# Anthe.net
KiCad netlist of a schematic drawn in EAGLE
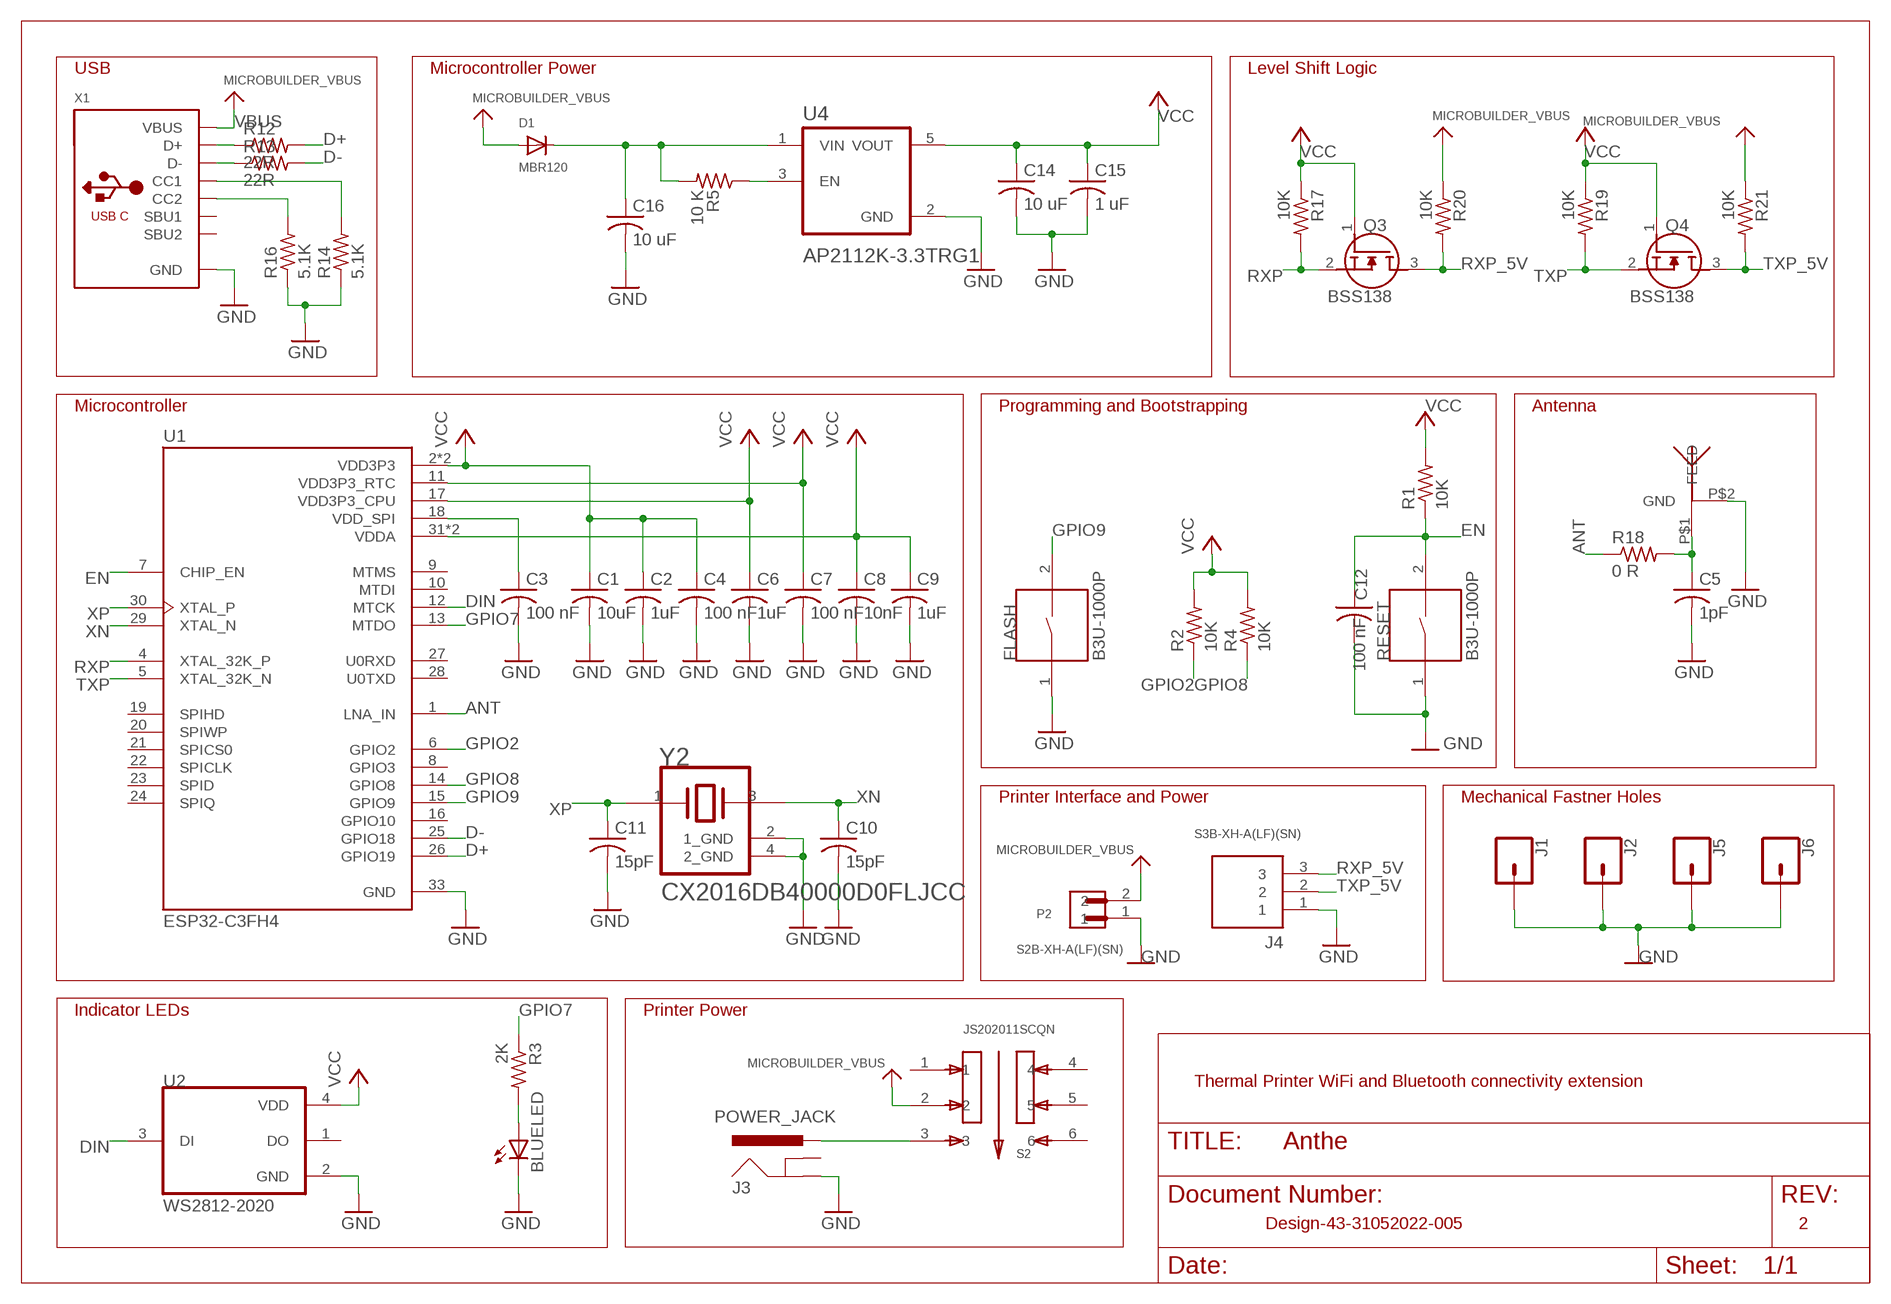
[diagram p0: schematic, sheet 1]

(export (version "E")
  (design (tool "Eeschema 10.0.6"))
  (components
    (comp (ref "BLUELED")
      (value "LEDCHIPLED_0603")
      (footprint "eagle-import:CHIPLED_0603")
      (libsource (lib "eagle-import") (part "LEDCHIPLED_0603"))
    )
    (comp (ref "C1")
      (value "10uF")
      (footprint "eagle-import:C0402")
      (libsource (lib "eagle-import") (part "C-USC0402"))
    )
    (comp (ref "C2")
      (value "1uF")
      (footprint "eagle-import:C0402")
      (libsource (lib "eagle-import") (part "C-USC0402"))
    )
    (comp (ref "C3")
      (value "100 nF")
      (footprint "eagle-import:C0402")
      (libsource (lib "eagle-import") (part "C-USC0402"))
    )
    (comp (ref "C4")
      (value "100 nF")
      (footprint "eagle-import:C0402")
      (libsource (lib "eagle-import") (part "C-USC0402"))
    )
    (comp (ref "C5")
      (value "1pF")
      (footprint "eagle-import:C0402")
      (libsource (lib "eagle-import") (part "C-USC0402"))
    )
    (comp (ref "C6")
      (value "1uF")
      (footprint "eagle-import:C0402")
      (libsource (lib "eagle-import") (part "C-USC0402"))
    )
    (comp (ref "C7")
      (value "100 nF")
      (footprint "eagle-import:C0402")
      (libsource (lib "eagle-import") (part "C-USC0402"))
    )
    (comp (ref "C8")
      (value "10nF")
      (footprint "eagle-import:C0402")
      (libsource (lib "eagle-import") (part "C-USC0402"))
    )
    (comp (ref "C9")
      (value "1uF")
      (footprint "eagle-import:C0402")
      (libsource (lib "eagle-import") (part "C-USC0402"))
    )
    (comp (ref "C10")
      (value "15pF")
      (footprint "eagle-import:C0402")
      (libsource (lib "eagle-import") (part "C-USC0402"))
    )
    (comp (ref "C11")
      (value "15pF")
      (footprint "eagle-import:C0402")
      (libsource (lib "eagle-import") (part "C-USC0402"))
    )
    (comp (ref "C12")
      (value "100 nF")
      (footprint "eagle-import:C0402")
      (libsource (lib "eagle-import") (part "C-USC0402"))
    )
    (comp (ref "C14")
      (value "10 uF")
      (footprint "eagle-import:C0402")
      (libsource (lib "eagle-import") (part "C-USC0402"))
    )
    (comp (ref "C15")
      (value "1 uF")
      (footprint "eagle-import:C0402")
      (libsource (lib "eagle-import") (part "C-USC0402"))
    )
    (comp (ref "C16")
      (value "10 uF")
      (footprint "eagle-import:C0402")
      (libsource (lib "eagle-import") (part "C-USC0402"))
    )
    (comp (ref "D1")
      (value "MBR120")
      (footprint "eagle-import:SOD-123")
      (libsource (lib "eagle-import") (part "DIODESOD-123"))
    )
    (comp (ref "FLASH")
      (value "B3U-1000P")
      (footprint "eagle-import:SW_B3U-1000P")
      (fields (field (name "MF") "Omron"))
      (libsource (lib "eagle-import") (part "B3U-1000P"))
    )
    (comp (ref "J1")
      (value "CONN_01PTH_2MM")
      (footprint "eagle-import:1X01_2MM")
      (libsource (lib "eagle-import") (part "CONN_01PTH_2MM"))
    )
    (comp (ref "J2")
      (value "CONN_01PTH_2MM")
      (footprint "eagle-import:1X01_2MM")
      (libsource (lib "eagle-import") (part "CONN_01PTH_2MM"))
    )
    (comp (ref "J3")
      (value "POWER_JACK")
      (footprint "eagle-import:POWER_JACK_PTH")
      (libsource (lib "eagle-import") (part "POWER_JACK"))
    )
    (comp (ref "J4")
      (value "S3B-XH-A(LF)(SN)")
      (footprint "eagle-import:JST_S3B-XH-A(LF)(SN)")
      (fields (field (name "MF") "JST Sales America Inc."))
      (libsource (lib "eagle-import") (part "S3B-XH-A(LF)(SN)"))
    )
    (comp (ref "J5")
      (value "CONN_01PTH_2MM")
      (footprint "eagle-import:1X01_2MM")
      (libsource (lib "eagle-import") (part "CONN_01PTH_2MM"))
    )
    (comp (ref "J6")
      (value "CONN_01PTH_2MM")
      (footprint "eagle-import:1X01_2MM")
      (libsource (lib "eagle-import") (part "CONN_01PTH_2MM"))
    )
    (comp (ref "P2")
      (value "S2B-XH-A(LF)(SN)")
      (footprint "eagle-import:JST_S2B-XH-A(LF)(SN)")
      (fields (field (name "MF") "JST Sales") (field (name "MP") "S2B-XH-A (LF)(SN)"))
      (libsource (lib "eagle-import") (part "S2B-XH-A(LF)(SN)"))
    )
    (comp (ref "Q3")
      (value "BSS138")
      (footprint "eagle-import:SOT95P240X120-3N")
      (fields (field (name "MOUSER_PART_NUMBER") "512-BSS138"))
      (libsource (lib "eagle-import") (part "BSS138"))
    )
    (comp (ref "Q4")
      (value "BSS138")
      (footprint "eagle-import:SOT95P240X120-3N")
      (fields (field (name "MOUSER_PART_NUMBER") "512-BSS138"))
      (libsource (lib "eagle-import") (part "BSS138"))
    )
    (comp (ref "R1")
      (value "10K")
      (footprint "eagle-import:R0402")
      (libsource (lib "eagle-import") (part "R-US_R0402"))
    )
    (comp (ref "R2")
      (value "10K")
      (footprint "eagle-import:R0402")
      (libsource (lib "eagle-import") (part "R-US_R0402"))
    )
    (comp (ref "R3")
      (value "2K")
      (footprint "eagle-import:R0402")
      (libsource (lib "eagle-import") (part "R-US_R0402"))
    )
    (comp (ref "R4")
      (value "10K")
      (footprint "eagle-import:R0402")
      (libsource (lib "eagle-import") (part "R-US_R0402"))
    )
    (comp (ref "R5")
      (value "10 K")
      (footprint "eagle-import:R0402")
      (libsource (lib "eagle-import") (part "R-US_R0402"))
    )
    (comp (ref "R12")
      (value "22R")
      (footprint "eagle-import:R0402")
      (libsource (lib "eagle-import") (part "R-US_R0402"))
    )
    (comp (ref "R13")
      (value "22R")
      (footprint "eagle-import:R0402")
      (libsource (lib "eagle-import") (part "R-US_R0402"))
    )
    (comp (ref "R14")
      (value "5.1K")
      (footprint "eagle-import:R0402")
      (libsource (lib "eagle-import") (part "R-US_R0402"))
    )
    (comp (ref "R16")
      (value "5.1K")
      (footprint "eagle-import:R0402")
      (libsource (lib "eagle-import") (part "R-US_R0402"))
    )
    (comp (ref "R17")
      (value "10K")
      (footprint "eagle-import:R0402")
      (libsource (lib "eagle-import") (part "R-US_R0402"))
    )
    (comp (ref "R18")
      (value "0 R")
      (footprint "eagle-import:R0402")
      (libsource (lib "eagle-import") (part "R-US_R0402"))
    )
    (comp (ref "R19")
      (value "10K")
      (footprint "eagle-import:R0402")
      (libsource (lib "eagle-import") (part "R-US_R0402"))
    )
    (comp (ref "R20")
      (value "10K")
      (footprint "eagle-import:R0402")
      (libsource (lib "eagle-import") (part "R-US_R0402"))
    )
    (comp (ref "R21")
      (value "10K")
      (footprint "eagle-import:R0402")
      (libsource (lib "eagle-import") (part "R-US_R0402"))
    )
    (comp (ref "RESET")
      (value "B3U-1000P")
      (footprint "eagle-import:SW_B3U-1000P")
      (fields (field (name "MF") "Omron"))
      (libsource (lib "eagle-import") (part "B3U-1000P"))
    )
    (comp (ref "S2")
      (value "JS202011SCQN")
      (footprint "eagle-import:SW_JS202011SCQN")
      (fields (field (name "MF") "C&K"))
      (libsource (lib "eagle-import") (part "JS202011SCQN"))
    )
    (comp (ref "U$3")
      (value "PCB_ANTENNA_WIFI")
      (footprint "eagle-import:WIFI_ANTENNA")
      (libsource (lib "eagle-import") (part "PCB_ANTENNA_WIFI"))
    )
    (comp (ref "U1")
      (value "ESP32-C3FH4")
      (footprint "eagle-import:QFN50P500X500X90-33N")
      (fields (field (name "MF") "Espressif Systems"))
      (libsource (lib "eagle-import") (part "ESP32-C3FH4"))
    )
    (comp (ref "U2")
      (value "WS2812-2020")
      (footprint "eagle-import:LED_WS2812-2020")
      (fields (field (name "MF") "Worldsemi"))
      (libsource (lib "eagle-import") (part "WS2812-2020"))
    )
    (comp (ref "U4")
      (value "AP2112K-3.3TRG1")
      (footprint "eagle-import:SOT95P285X140-5N")
      (fields (field (name "MF") "Diodes Inc."))
      (libsource (lib "eagle-import") (part "AP2112K-3.3TRG1"))
    )
    (comp (ref "X1")
      (value "MICROBUILDER_USB_C")
      (footprint "eagle-import:MICROBUILDER_USB_C_CUSB31-CFM2AX-01-X")
      (libsource (lib "eagle-import") (part "MICROBUILDER_USB_C"))
    )
    (comp (ref "Y2")
      (value "KYOCERA_INTERNATIONAL_INC._ELECTRONIC_COMPONENTS_CX2016DB40000D0FLJCCKYOCERA_INTERNATIONAL_INC._ELECTRONIC_COMPONENTS_CX2016DB40000D0FLJCC_0_0")
      (footprint "eagle-import:KYOCERA_INTERNATIONAL_INC._ELECTRONIC_COMPONENTS_CX2016DB40000D0FLJCC_0")
      (fields
        (field (name "DIGIKEY_PART_NUMBER") "1253-1120-1-ND")
        (field (name "MF") "Kyocera International Inc. Electronic Components")
        (field (name "MOUSER_PART_NUMBER") "581-CX2016DB40DFLJCC")
      )
      (libsource (lib "eagle-import") (part "KYOCERA_INTERNATIONAL_INC._ELECTRONIC_COMPONENTS_CX2016DB40000D0FLJCCKYOCERA_INTERNATIONAL_INC._ELECTRONIC_COMPONENTS_CX2016DB40000D0FLJCC_0_0"))
    )
  )
  (nets
    (net (code "1") (name "/ANT") (class "Default")
      (node (ref "R18") (pin "1") (pinfunction "1_1") (pintype "passive"))
      (node (ref "U1") (pin "1") (pinfunction "LNA_IN_1") (pintype "bidirectional"))
    )
    (net (code "2") (name "/D+") (class "Default")
      (node (ref "R12") (pin "2") (pinfunction "2_2") (pintype "passive"))
      (node (ref "U1") (pin "26") (pinfunction "GPIO19_26") (pintype "bidirectional"))
    )
    (net (code "3") (name "/D-") (class "Default")
      (node (ref "R13") (pin "2") (pinfunction "2_2") (pintype "passive"))
      (node (ref "U1") (pin "25") (pinfunction "GPIO18_25") (pintype "bidirectional"))
    )
    (net (code "4") (name "/DIN") (class "Default")
      (node (ref "U1") (pin "12") (pinfunction "MTCK_12") (pintype "bidirectional"))
      (node (ref "U2") (pin "3") (pinfunction "DI_3") (pintype "input"))
    )
    (net (code "5") (name "/EN") (class "Default")
      (node (ref "C12") (pin "1") (pinfunction "1_1") (pintype "passive"))
      (node (ref "R1") (pin "1") (pinfunction "1_1") (pintype "passive"))
      (node (ref "RESET") (pin "2") (pinfunction "2_2") (pintype "passive"))
      (node (ref "U1") (pin "7") (pinfunction "CHIP_EN_7") (pintype "input"))
    )
    (net (code "6") (name "/GPIO2") (class "Default")
      (node (ref "R2") (pin "1") (pinfunction "1_1") (pintype "passive"))
      (node (ref "U1") (pin "6") (pinfunction "GPIO2_6") (pintype "bidirectional"))
    )
    (net (code "7") (name "/GPIO7") (class "Default")
      (node (ref "R3") (pin "1") (pinfunction "1_1") (pintype "passive"))
      (node (ref "U1") (pin "13") (pinfunction "MTDO_13") (pintype "bidirectional"))
    )
    (net (code "8") (name "/GPIO8") (class "Default")
      (node (ref "R4") (pin "1") (pinfunction "1_1") (pintype "passive"))
      (node (ref "U1") (pin "14") (pinfunction "GPIO8_14") (pintype "bidirectional"))
    )
    (net (code "9") (name "/GPIO9") (class "Default")
      (node (ref "FLASH") (pin "2") (pinfunction "2_2") (pintype "passive"))
      (node (ref "U1") (pin "15") (pinfunction "GPIO9_15") (pintype "bidirectional"))
    )
    (net (code "10") (name "/RXP") (class "Default")
      (node (ref "Q3") (pin "2") (pinfunction "S_2") (pintype "bidirectional"))
      (node (ref "R17") (pin "2") (pinfunction "2_2") (pintype "passive"))
      (node (ref "U1") (pin "4") (pinfunction "XTAL_32K_P_4") (pintype "bidirectional"))
    )
    (net (code "11") (name "/RXP_5V") (class "Default")
      (node (ref "J4") (pin "3") (pinfunction "3_3") (pintype "passive"))
      (node (ref "Q3") (pin "3") (pinfunction "D_3") (pintype "bidirectional"))
      (node (ref "R20") (pin "2") (pinfunction "2_2") (pintype "passive"))
    )
    (net (code "12") (name "/TXP") (class "Default")
      (node (ref "Q4") (pin "2") (pinfunction "S_2") (pintype "bidirectional"))
      (node (ref "R19") (pin "2") (pinfunction "2_2") (pintype "passive"))
      (node (ref "U1") (pin "5") (pinfunction "XTAL_32K_N_5") (pintype "bidirectional"))
    )
    (net (code "13") (name "/TXP_5V") (class "Default")
      (node (ref "J4") (pin "2") (pinfunction "2_2") (pintype "passive"))
      (node (ref "Q4") (pin "3") (pinfunction "D_3") (pintype "bidirectional"))
      (node (ref "R21") (pin "2") (pinfunction "2_2") (pintype "passive"))
    )
    (net (code "14") (name "/XN") (class "Default")
      (node (ref "C10") (pin "1") (pinfunction "1_1") (pintype "passive"))
      (node (ref "U1") (pin "29") (pinfunction "XTAL_N_29") (pintype "output"))
      (node (ref "Y2") (pin "3") (pinfunction "3_3") (pintype "passive"))
    )
    (net (code "15") (name "/XP") (class "Default")
      (node (ref "C11") (pin "1") (pinfunction "1_1") (pintype "passive"))
      (node (ref "U1") (pin "30") (pinfunction "XTAL_P_30") (pintype "input"))
      (node (ref "Y2") (pin "1") (pinfunction "1_1") (pintype "passive"))
    )
    (net (code "16") (name "GND") (class "Default")
      (node (ref "BLUELED") (pin "C") (pinfunction "C_C") (pintype "passive"))
      (node (ref "C1") (pin "2") (pinfunction "2_2") (pintype "passive"))
      (node (ref "C10") (pin "2") (pinfunction "2_2") (pintype "passive"))
      (node (ref "C11") (pin "2") (pinfunction "2_2") (pintype "passive"))
      (node (ref "C12") (pin "2") (pinfunction "2_2") (pintype "passive"))
      (node (ref "C14") (pin "2") (pinfunction "2_2") (pintype "passive"))
      (node (ref "C15") (pin "2") (pinfunction "2_2") (pintype "passive"))
      (node (ref "C16") (pin "2") (pinfunction "2_2") (pintype "passive"))
      (node (ref "C2") (pin "2") (pinfunction "2_2") (pintype "passive"))
      (node (ref "C3") (pin "2") (pinfunction "2_2") (pintype "passive"))
      (node (ref "C4") (pin "2") (pinfunction "2_2") (pintype "passive"))
      (node (ref "C5") (pin "2") (pinfunction "2_2") (pintype "passive"))
      (node (ref "C6") (pin "2") (pinfunction "2_2") (pintype "passive"))
      (node (ref "C7") (pin "2") (pinfunction "2_2") (pintype "passive"))
      (node (ref "C8") (pin "2") (pinfunction "2_2") (pintype "passive"))
      (node (ref "C9") (pin "2") (pinfunction "2_2") (pintype "passive"))
      (node (ref "FLASH") (pin "1") (pinfunction "1_1") (pintype "passive"))
      (node (ref "J1") (pin "1") (pinfunction "1_1") (pintype "passive"))
      (node (ref "J2") (pin "1") (pinfunction "1_1") (pintype "passive"))
      (node (ref "J3") (pin "GND") (pinfunction "GND_GND") (pintype "bidirectional"))
      (node (ref "J4") (pin "1") (pinfunction "1_1") (pintype "passive"))
      (node (ref "J5") (pin "1") (pinfunction "1_1") (pintype "passive"))
      (node (ref "J6") (pin "1") (pinfunction "1_1") (pintype "passive"))
      (node (ref "P2") (pin "1") (pinfunction "1_1") (pintype "passive"))
      (node (ref "R14") (pin "1") (pinfunction "1_1") (pintype "passive"))
      (node (ref "R16") (pin "1") (pinfunction "1_1") (pintype "passive"))
      (node (ref "RESET") (pin "1") (pinfunction "1_1") (pintype "passive"))
      (node (ref "U$3") (pin "P$2") (pinfunction "GND_P$2") (pintype "output"))
      (node (ref "U1") (pin "33") (pinfunction "GND_33") (pintype "power_in"))
      (node (ref "U2") (pin "2") (pinfunction "GND_2") (pintype "power_in"))
      (node (ref "U4") (pin "2") (pinfunction "GND_2") (pintype "power_in"))
      (node (ref "X1") (pin "A1B12") (pinfunction "GND_A1B12") (pintype "power_in"))
      (node (ref "X1") (pin "B1A12") (pinfunction "GND_B1A12") (pintype "power_in"))
      (node (ref "Y2") (pin "2") (pinfunction "1_GND_2") (pintype "power_in"))
      (node (ref "Y2") (pin "4") (pinfunction "2_GND_4") (pintype "power_in"))
    )
    (net (code "17") (name "MICROBUILDER_VBUS") (class "Default")
      (node (ref "D1") (pin "A") (pinfunction "A_A") (pintype "passive"))
      (node (ref "P2") (pin "2") (pinfunction "2_2") (pintype "passive"))
      (node (ref "R20") (pin "1") (pinfunction "1_1") (pintype "passive"))
      (node (ref "R21") (pin "1") (pinfunction "1_1") (pintype "passive"))
      (node (ref "S2") (pin "2") (pinfunction "2_2") (pintype "passive"))
      (node (ref "X1") (pin "A4B9") (pinfunction "VBUS_A4B9") (pintype "power_in"))
      (node (ref "X1") (pin "B4A9") (pinfunction "VBUS_B4A9") (pintype "power_in"))
    )
    (net (code "18") (name "Net-(BLUELED-PadA)") (class "Default")
      (node (ref "BLUELED") (pin "A") (pinfunction "A_A") (pintype "passive"))
      (node (ref "R3") (pin "2") (pinfunction "2_2") (pintype "passive"))
    )
    (net (code "19") (name "Net-(J3-PadPWR)") (class "Default")
      (node (ref "J3") (pin "PWR") (pinfunction "PWR_PWR") (pintype "bidirectional"))
      (node (ref "S2") (pin "3") (pinfunction "3_3") (pintype "passive"))
    )
    (net (code "20") (name "Net-(R12-Pad1)") (class "Default")
      (node (ref "R12") (pin "1") (pinfunction "1_1") (pintype "passive"))
      (node (ref "X1") (pin "A6") (pinfunction "D+_A6") (pintype "bidirectional"))
      (node (ref "X1") (pin "B6") (pinfunction "D+_B6") (pintype "bidirectional"))
    )
    (net (code "21") (name "Net-(R13-Pad1)") (class "Default")
      (node (ref "R13") (pin "1") (pinfunction "1_1") (pintype "passive"))
      (node (ref "X1") (pin "A7") (pinfunction "D-_A7") (pintype "bidirectional"))
      (node (ref "X1") (pin "B7") (pinfunction "D-_B7") (pintype "bidirectional"))
    )
    (net (code "22") (name "Net-(U$3-FEED)") (class "Default")
      (node (ref "C5") (pin "1") (pinfunction "1_1") (pintype "passive"))
      (node (ref "R18") (pin "2") (pinfunction "2_2") (pintype "passive"))
      (node (ref "U$3") (pin "P$1") (pinfunction "FEED_P$1") (pintype "input"))
    )
    (net (code "23") (name "Net-(U1-VDD_SPI)") (class "Default")
      (node (ref "C3") (pin "1") (pinfunction "1_1") (pintype "passive"))
      (node (ref "U1") (pin "18") (pinfunction "VDD_SPI_18") (pintype "power_in"))
    )
    (net (code "24") (name "Net-(U4-EN)") (class "Default")
      (node (ref "R5") (pin "1") (pinfunction "1_1") (pintype "passive"))
      (node (ref "U4") (pin "3") (pinfunction "EN_3") (pintype "input"))
    )
    (net (code "25") (name "Net-(U4-VIN)") (class "Default")
      (node (ref "C16") (pin "1") (pinfunction "1_1") (pintype "passive"))
      (node (ref "D1") (pin "C") (pinfunction "C_C") (pintype "passive"))
      (node (ref "R5") (pin "2") (pinfunction "2_2") (pintype "passive"))
      (node (ref "U4") (pin "1") (pinfunction "VIN_1") (pintype "power_in"))
    )
    (net (code "26") (name "Net-(X1-CC1)") (class "Default")
      (node (ref "R14") (pin "2") (pinfunction "2_2") (pintype "passive"))
      (node (ref "X1") (pin "A5") (pinfunction "CC1_A5") (pintype "bidirectional"))
    )
    (net (code "27") (name "Net-(X1-CC2)") (class "Default")
      (node (ref "R16") (pin "2") (pinfunction "2_2") (pintype "passive"))
      (node (ref "X1") (pin "B5") (pinfunction "CC2_B5") (pintype "bidirectional"))
    )
    (net (code "28") (name "VCC") (class "Default")
      (node (ref "C1") (pin "1") (pinfunction "1_1") (pintype "passive"))
      (node (ref "C14") (pin "1") (pinfunction "1_1") (pintype "passive"))
      (node (ref "C15") (pin "1") (pinfunction "1_1") (pintype "passive"))
      (node (ref "C2") (pin "1") (pinfunction "1_1") (pintype "passive"))
      (node (ref "C4") (pin "1") (pinfunction "1_1") (pintype "passive"))
      (node (ref "C6") (pin "1") (pinfunction "1_1") (pintype "passive"))
      (node (ref "C7") (pin "1") (pinfunction "1_1") (pintype "passive"))
      (node (ref "C8") (pin "1") (pinfunction "1_1") (pintype "passive"))
      (node (ref "C9") (pin "1") (pinfunction "1_1") (pintype "passive"))
      (node (ref "Q3") (pin "1") (pinfunction "G_1") (pintype "bidirectional"))
      (node (ref "Q4") (pin "1") (pinfunction "G_1") (pintype "bidirectional"))
      (node (ref "R1") (pin "2") (pinfunction "2_2") (pintype "passive"))
      (node (ref "R17") (pin "1") (pinfunction "1_1") (pintype "passive"))
      (node (ref "R19") (pin "1") (pinfunction "1_1") (pintype "passive"))
      (node (ref "R2") (pin "2") (pinfunction "2_2") (pintype "passive"))
      (node (ref "R4") (pin "2") (pinfunction "2_2") (pintype "passive"))
      (node (ref "U1") (pin "11") (pinfunction "VDD3P3_RTC_11") (pintype "power_in"))
      (node (ref "U1") (pin "17") (pinfunction "VDD3P3_CPU_17") (pintype "power_in"))
      (node (ref "U1") (pin "2") (pinfunction "VDD3P3_2") (pintype "power_in"))
      (node (ref "U1") (pin "3") (pinfunction "VDD3P3_3") (pintype "power_in"))
      (node (ref "U1") (pin "31") (pinfunction "VDDA_31") (pintype "power_in"))
      (node (ref "U1") (pin "32") (pinfunction "VDDA_32") (pintype "power_in"))
      (node (ref "U2") (pin "4") (pinfunction "VDD_4") (pintype "power_in"))
      (node (ref "U4") (pin "5") (pinfunction "VOUT_5") (pintype "power_in"))
    )
    (net (code "29") (name "unconnected-(J3-PadGNDBREAK)") (class "Default")
      (node (ref "J3") (pin "GNDBREAK") (pinfunction "GNDBREAK_GNDBREAK") (pintype "bidirectional"))
    )
    (net (code "30") (name "unconnected-(S2-Pad1)") (class "Default")
      (node (ref "S2") (pin "1") (pinfunction "1_1") (pintype "passive"))
    )
    (net (code "31") (name "unconnected-(S2-Pad4)") (class "Default")
      (node (ref "S2") (pin "4") (pinfunction "4_4") (pintype "passive"))
    )
    (net (code "32") (name "unconnected-(S2-Pad5)") (class "Default")
      (node (ref "S2") (pin "5") (pinfunction "5_5") (pintype "passive"))
    )
    (net (code "33") (name "unconnected-(S2-Pad6)") (class "Default")
      (node (ref "S2") (pin "6") (pinfunction "6_6") (pintype "passive"))
    )
    (net (code "34") (name "unconnected-(U1-GPIO3-Pad8)") (class "Default")
      (node (ref "U1") (pin "8") (pinfunction "GPIO3_8") (pintype "bidirectional"))
    )
    (net (code "35") (name "unconnected-(U1-GPIO10-Pad16)") (class "Default")
      (node (ref "U1") (pin "16") (pinfunction "GPIO10_16") (pintype "bidirectional"))
    )
    (net (code "36") (name "unconnected-(U1-MTDI-Pad10)") (class "Default")
      (node (ref "U1") (pin "10") (pinfunction "MTDI_10") (pintype "bidirectional"))
    )
    (net (code "37") (name "unconnected-(U1-MTMS-Pad9)") (class "Default")
      (node (ref "U1") (pin "9") (pinfunction "MTMS_9") (pintype "bidirectional"))
    )
    (net (code "38") (name "unconnected-(U1-SPICLK-Pad22)") (class "Default")
      (node (ref "U1") (pin "22") (pinfunction "SPICLK_22") (pintype "bidirectional"))
    )
    (net (code "39") (name "unconnected-(U1-SPICS0-Pad21)") (class "Default")
      (node (ref "U1") (pin "21") (pinfunction "SPICS0_21") (pintype "bidirectional"))
    )
    (net (code "40") (name "unconnected-(U1-SPID-Pad23)") (class "Default")
      (node (ref "U1") (pin "23") (pinfunction "SPID_23") (pintype "bidirectional"))
    )
    (net (code "41") (name "unconnected-(U1-SPIHD-Pad19)") (class "Default")
      (node (ref "U1") (pin "19") (pinfunction "SPIHD_19") (pintype "bidirectional"))
    )
    (net (code "42") (name "unconnected-(U1-SPIQ-Pad24)") (class "Default")
      (node (ref "U1") (pin "24") (pinfunction "SPIQ_24") (pintype "bidirectional"))
    )
    (net (code "43") (name "unconnected-(U1-SPIWP-Pad20)") (class "Default")
      (node (ref "U1") (pin "20") (pinfunction "SPIWP_20") (pintype "bidirectional"))
    )
    (net (code "44") (name "unconnected-(U1-U0RXD-Pad27)") (class "Default")
      (node (ref "U1") (pin "27") (pinfunction "U0RXD_27") (pintype "bidirectional"))
    )
    (net (code "45") (name "unconnected-(U1-U0TXD-Pad28)") (class "Default")
      (node (ref "U1") (pin "28") (pinfunction "U0TXD_28") (pintype "bidirectional"))
    )
    (net (code "46") (name "unconnected-(U2-DO-Pad1)") (class "Default")
      (node (ref "U2") (pin "1") (pinfunction "DO_1") (pintype "output"))
    )
    (net (code "47") (name "unconnected-(X1-SBU1-PadA8)") (class "Default")
      (node (ref "X1") (pin "A8") (pinfunction "SBU1_A8") (pintype "bidirectional"))
    )
    (net (code "48") (name "unconnected-(X1-SBU2-PadB8)") (class "Default")
      (node (ref "X1") (pin "B8") (pinfunction "SBU2_B8") (pintype "bidirectional"))
    )
  )
)
